# CAN.net
KiCad netlist of a schematic drawn in Altium Designer
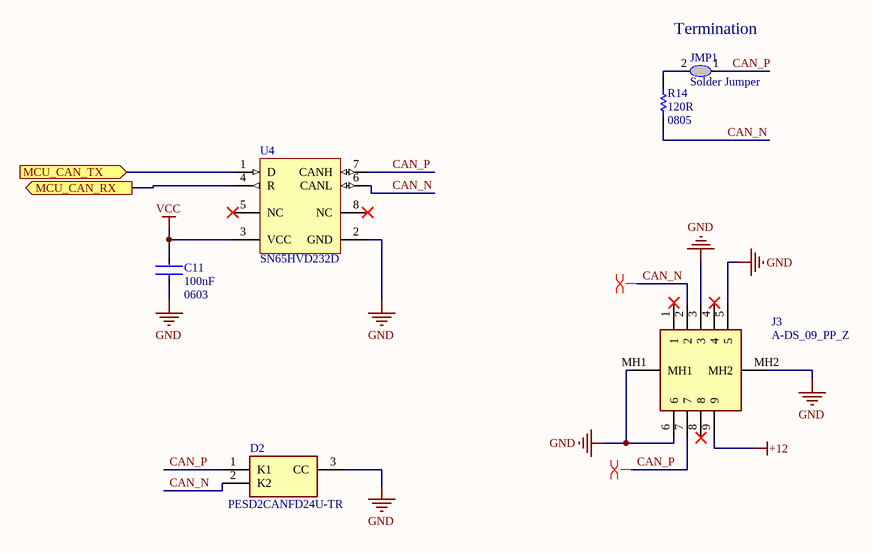
[diagram p0: CAN.SchDoc]

(export (version "E")
  (design (tool "Eeschema 10.0.6"))
  (components
    (comp (ref "C11")
      (value "CL10B104KB8WPNC")
      (footprint "FP-CL10-IPC_A")
      (description "Cap Ceramic 100nF 50V X7R ±10% Pad SMD 0603 +125°C T/R")
      (fields
        (field (name "CAPACITANCE") "100nF")
        (field (name "CASE/PACKAGE") "0603")
        (field (name "TOLERANCE") "10%")
      )
      (libsource (lib "Altium Content Vault") (part "b4654b650e69147ec39a6b967a45e02"))
    )
    (comp (ref "D2")
      (value "PESD2CANFD24U-TR")
      (footprint "SOT95P230X110-3N")
      (description "Diode")
      (fields (field (name "MOUSER PART NUMBER") "771-PESD2CANFD24U-TR"))
      (libsource (lib "WiCAN_lib") (part "PESD2CANFD24U-TR"))
    )
    (comp (ref "J3")
      (value "A-DS_09_PP_Z")
      (footprint "ADS09PPZ")
      (description "Connector")
      (fields (field (name "MANUFACTURER_PART_NUMBER") "A-DS 09 PP/Z"))
      (libsource (lib "WiCAN_lib") (part "A-DS_09_PP_Z"))
    )
    (comp (ref "JMP1")
      (value "Solder Jumper")
      (footprint "Solder Jumper")
      (libsource (lib "WiCAN_lib") (part "Solder Jumper"))
    )
    (comp (ref "R14")
      (value "ERJ-P06J121V")
      (footprint "RESC2013X70X40LL20T20")
      (fields
        (field (name "MANUFACTURER") "Panasonic")
        (field (name "RESISTANCE") "120R")
        (field (name "PACKAGE") "0805")
      )
      (libsource (lib "Altium Content Vault") (part "RES"))
    )
    (comp (ref "U4")
      (value "SN65HVD232D")
      (footprint "D0008A_L")
      (description "3.3 V CAN Transceiver, 17 mA, -40 to 85 degC, 8-pin SOIC (D), Green (RoHS & no Sb/Br)")
      (fields (field (name "MANUFACTURER") "Texas Instruments"))
      (libsource (lib "Altium Content Vault") (part "TI-SN65HVD232-SOIC_D-8"))
    )
  )
  (nets
    (net (code "1") (name "+12") (class "Default")
      (node (ref "J3") (pin "9") (pinfunction "9_9") (pintype "passive"))
    )
    (net (code "2") (name "/CAN_N") (class "Default")
      (node (ref "D2") (pin "2") (pinfunction "K2_2") (pintype "passive"))
      (node (ref "J3") (pin "2") (pinfunction "2_2") (pintype "passive"))
      (node (ref "R14") (pin "2") (pinfunction "2_2") (pintype "passive"))
      (node (ref "U4") (pin "6") (pinfunction "CANL_6") (pintype "bidirectional"))
    )
    (net (code "3") (name "/CAN_P") (class "Default")
      (node (ref "D2") (pin "1") (pinfunction "K1_1") (pintype "passive"))
      (node (ref "J3") (pin "7") (pinfunction "7_7") (pintype "passive"))
      (node (ref "JMP1") (pin "1") (pinfunction "1_1") (pintype "passive"))
      (node (ref "U4") (pin "7") (pinfunction "CANH_7") (pintype "bidirectional"))
    )
    (net (code "4") (name "/MCU_CAN_RX") (class "Default")
      (node (ref "U4") (pin "4") (pinfunction "R_4") (pintype "output"))
    )
    (net (code "5") (name "/MCU_CAN_TX") (class "Default")
      (node (ref "U4") (pin "1") (pinfunction "D_1") (pintype "input"))
    )
    (net (code "6") (name "GND") (class "Default")
      (node (ref "C11") (pin "1") (pinfunction "1_1") (pintype "passive"))
      (node (ref "D2") (pin "3") (pinfunction "CC_3") (pintype "passive"))
      (node (ref "J3") (pin "3") (pinfunction "3_3") (pintype "passive"))
      (node (ref "J3") (pin "5") (pinfunction "5_5") (pintype "passive"))
      (node (ref "J3") (pin "6") (pinfunction "6_6") (pintype "passive"))
      (node (ref "J3") (pin "MH1") (pinfunction "MH1_MH1") (pintype "passive"))
      (node (ref "J3") (pin "MH2") (pinfunction "MH2_MH2") (pintype "passive"))
      (node (ref "U4") (pin "2") (pinfunction "GND_2") (pintype "power_in"))
    )
    (net (code "7") (name "Net-(JMP1-Pad2)") (class "Default")
      (node (ref "JMP1") (pin "2") (pinfunction "2_2") (pintype "passive"))
      (node (ref "R14") (pin "1") (pinfunction "1_1") (pintype "passive"))
    )
    (net (code "8") (name "VCC") (class "Default")
      (node (ref "C11") (pin "2") (pinfunction "2_2") (pintype "passive"))
      (node (ref "U4") (pin "3") (pinfunction "VCC_3") (pintype "power_in"))
    )
    (net (code "9") (name "unconnected-(J3-Pad1)") (class "Default")
      (node (ref "J3") (pin "1") (pinfunction "1_1") (pintype "passive+no_connect"))
    )
    (net (code "10") (name "unconnected-(J3-Pad4)") (class "Default")
      (node (ref "J3") (pin "4") (pinfunction "4_4") (pintype "passive+no_connect"))
    )
    (net (code "11") (name "unconnected-(J3-Pad8)") (class "Default")
      (node (ref "J3") (pin "8") (pinfunction "8_8") (pintype "passive+no_connect"))
    )
    (net (code "12") (name "unconnected-(U4-NC-Pad5)") (class "Default")
      (node (ref "U4") (pin "5") (pinfunction "NC_5") (pintype "passive+no_connect"))
    )
    (net (code "13") (name "unconnected-(U4-NC-Pad8)") (class "Default")
      (node (ref "U4") (pin "8") (pinfunction "NC_8") (pintype "passive+no_connect"))
    )
  )
)
